# interface_dac_sma_feedback_2PS_LM317_ADC.net
KiCad netlist of a schematic drawn in EAGLE
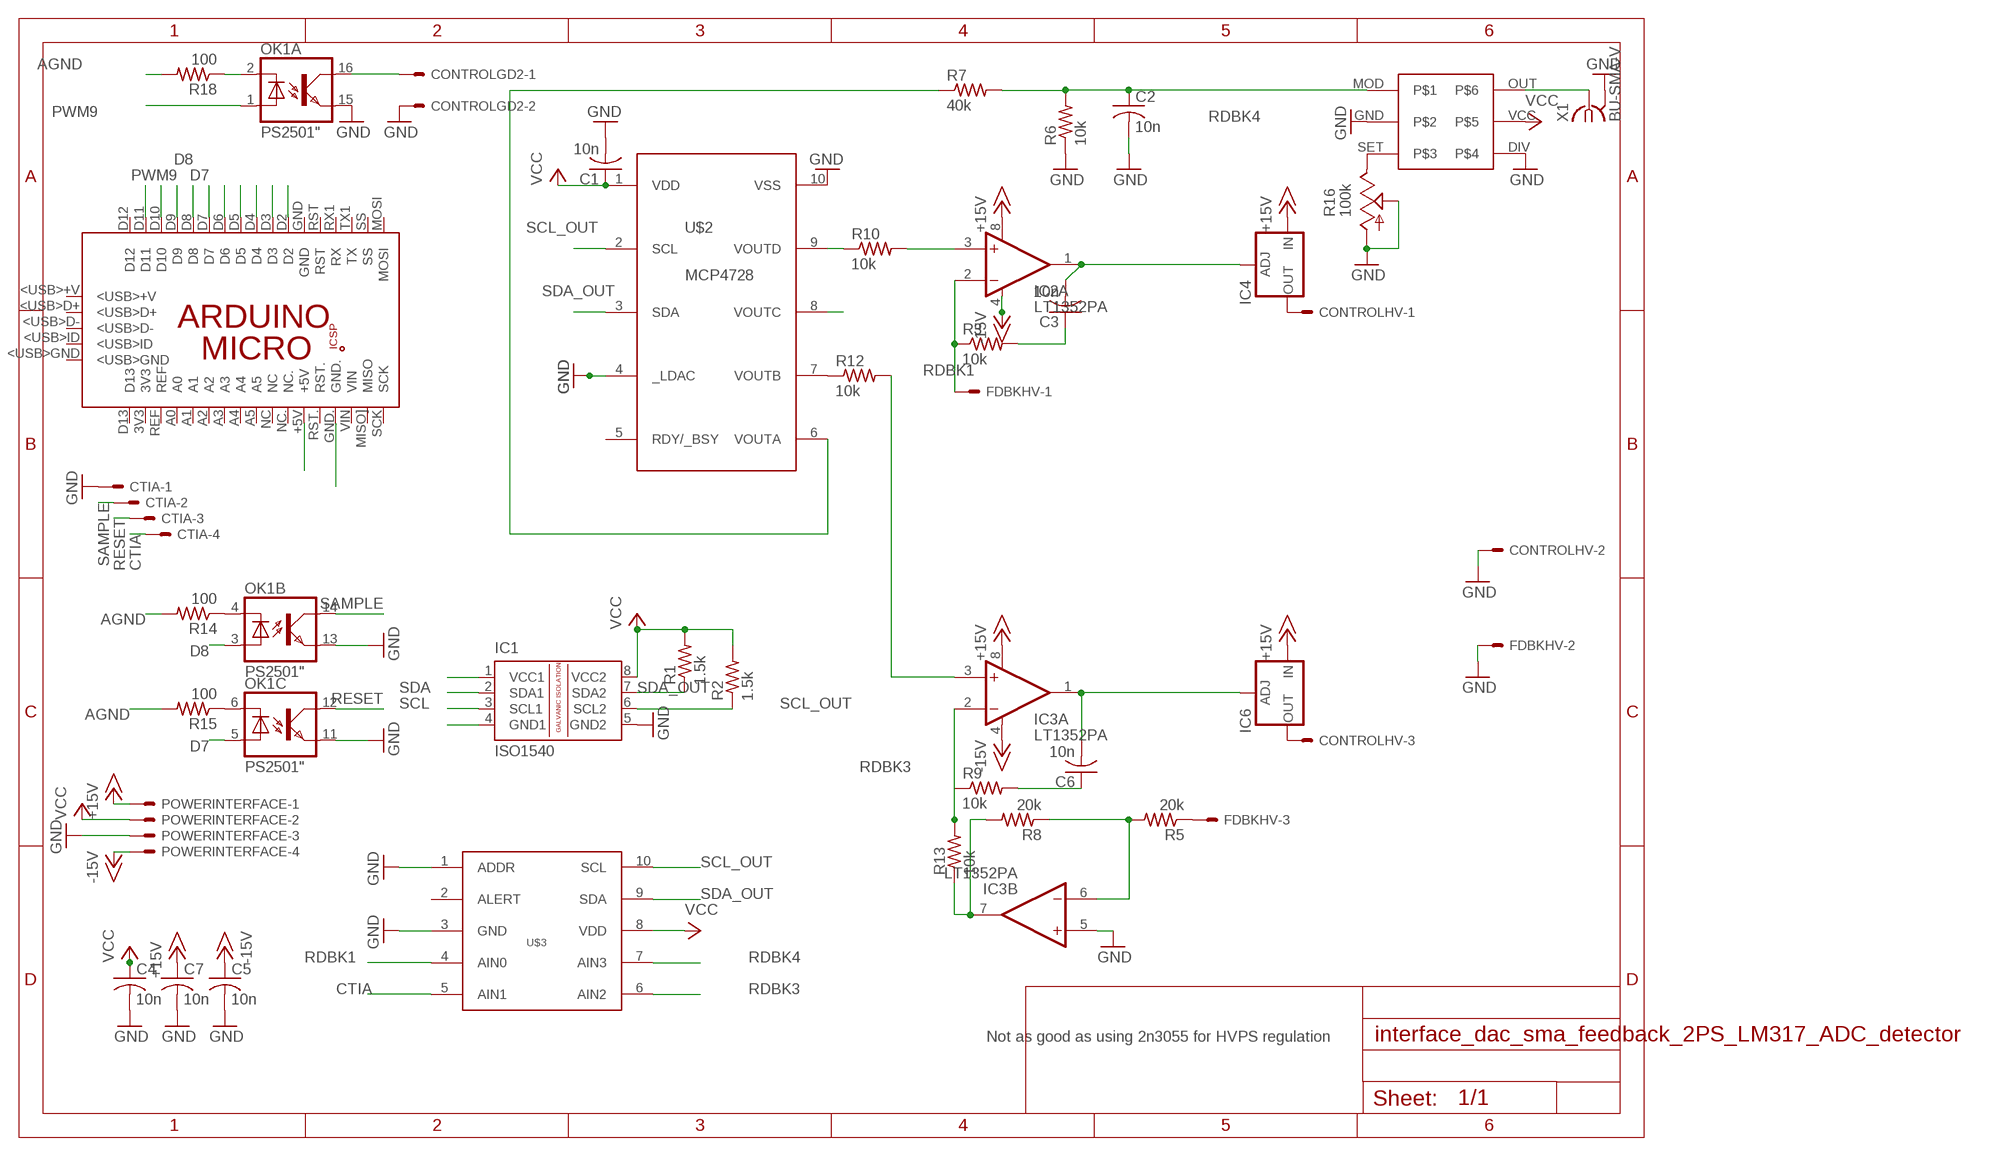
[diagram p0: schematic, sheet 1]

(export (version "E")
  (design (tool "Eeschema 10.0.6"))
  (components
    (comp (ref "C1")
      (value "10n")
      (footprint "eagle-import:C050-024X044")
      (libsource (lib "eagle-import") (part "C-US050-024X044"))
    )
    (comp (ref "C2")
      (value "10n")
      (footprint "eagle-import:C050-024X044")
      (libsource (lib "eagle-import") (part "resistor_C-US050-024X044"))
    )
    (comp (ref "C3")
      (value "10n")
      (footprint "eagle-import:C050-024X044")
      (libsource (lib "eagle-import") (part "resistor_C-US050-024X044"))
    )
    (comp (ref "C4")
      (value "10n")
      (footprint "eagle-import:C050-024X044")
      (libsource (lib "eagle-import") (part "resistor_C-US050-024X044"))
    )
    (comp (ref "C5")
      (value "10n")
      (footprint "eagle-import:C050-024X044")
      (libsource (lib "eagle-import") (part "resistor_C-US050-024X044"))
    )
    (comp (ref "C6")
      (value "10n")
      (footprint "eagle-import:C050-024X044")
      (libsource (lib "eagle-import") (part "resistor_C-US050-024X044"))
    )
    (comp (ref "C7")
      (value "10n")
      (footprint "eagle-import:C050-024X044")
      (libsource (lib "eagle-import") (part "resistor_C-US050-024X044"))
    )
    (comp (ref "CONTROLGD2")
      (value "KK-156-2")
      (footprint "eagle-import:KK-156-2")
      (libsource (lib "eagle-import") (part "KK-156-2"))
    )
    (comp (ref "CONTROLHV")
      (value "KK-156-3")
      (footprint "eagle-import:KK-156-3")
      (libsource (lib "eagle-import") (part "KK-156-3"))
    )
    (comp (ref "CTIA")
      (value "KK-156-4")
      (footprint "eagle-import:KK-156-4")
      (libsource (lib "eagle-import") (part "KK-156-4"))
    )
    (comp (ref "FDBKHV")
      (value "KK-156-3")
      (footprint "eagle-import:KK-156-3")
      (libsource (lib "eagle-import") (part "KK-156-3"))
    )
    (comp (ref "IC1")
      (value "ISO1540")
      (footprint "eagle-import:DIL08")
      (libsource (lib "eagle-import") (part "ISO1540"))
    )
    (comp (ref "IC2")
      (value "LT1352PA")
      (footprint "eagle-import:DIL08")
      (libsource (lib "eagle-import") (part "LT1352PA"))
    )
    (comp (ref "IC3")
      (value "LT1352PA")
      (footprint "eagle-import:DIL08")
      (libsource (lib "eagle-import") (part "LT1352PA"))
    )
    (comp (ref "IC4")
      (value "LM317-TO3")
      (footprint "eagle-import:TO3-K02")
      (libsource (lib "eagle-import") (part "LM317-TO3"))
    )
    (comp (ref "IC6")
      (value "LM317-TO3")
      (footprint "eagle-import:TO3-K02")
      (libsource (lib "eagle-import") (part "LM317-TO3"))
    )
    (comp (ref "OK1")
      (value "PS2501\"")
      (footprint "eagle-import:DIL16")
      (libsource (lib "eagle-import") (part "PS2501{dblquote}"))
    )
    (comp (ref "PCB1")
      (value "ARDUINO_MICRO")
      (footprint "eagle-import:ARDUINO_MICRO")
      (libsource (lib "eagle-import") (part "ARDUINO_MICRO"))
    )
    (comp (ref "POWERINTERFACE")
      (value "KK-156-4")
      (footprint "eagle-import:KK-156-4")
      (libsource (lib "eagle-import") (part "KK-156-4"))
    )
    (comp (ref "R1")
      (value "1.5k")
      (footprint "eagle-import:0207_12")
      (libsource (lib "eagle-import") (part "resistor_R-US_0207/12"))
    )
    (comp (ref "R2")
      (value "1.5k")
      (footprint "eagle-import:0207_12")
      (libsource (lib "eagle-import") (part "resistor_R-US_0207/12"))
    )
    (comp (ref "R3")
      (value "10k")
      (footprint "eagle-import:0207_12")
      (libsource (lib "eagle-import") (part "resistor_R-US_0207/12"))
    )
    (comp (ref "R5")
      (value "20k")
      (footprint "eagle-import:0207_12")
      (libsource (lib "eagle-import") (part "resistor_R-US_0207/12"))
    )
    (comp (ref "R6")
      (value "10k")
      (footprint "eagle-import:0207_12")
      (libsource (lib "eagle-import") (part "resistor_R-US_0207/12"))
    )
    (comp (ref "R7")
      (value "40k")
      (footprint "eagle-import:0207_12")
      (libsource (lib "eagle-import") (part "resistor_R-US_0207/12"))
    )
    (comp (ref "R8")
      (value "20k")
      (footprint "eagle-import:0207_12")
      (libsource (lib "eagle-import") (part "resistor_R-US_0207/12"))
    )
    (comp (ref "R9")
      (value "10k")
      (footprint "eagle-import:0207_12")
      (libsource (lib "eagle-import") (part "resistor_R-US_0207/12"))
    )
    (comp (ref "R10")
      (value "10k")
      (footprint "eagle-import:0207_12")
      (libsource (lib "eagle-import") (part "resistor_R-US_0207/12"))
    )
    (comp (ref "R12")
      (value "10k")
      (footprint "eagle-import:0207_12")
      (libsource (lib "eagle-import") (part "resistor_R-US_0207/12"))
    )
    (comp (ref "R13")
      (value "10k")
      (footprint "eagle-import:0207_12")
      (libsource (lib "eagle-import") (part "resistor_R-US_0207/12"))
    )
    (comp (ref "R14")
      (value "100")
      (footprint "eagle-import:0207_12")
      (libsource (lib "eagle-import") (part "R-US_0207/12"))
    )
    (comp (ref "R15")
      (value "100")
      (footprint "eagle-import:0207_12")
      (libsource (lib "eagle-import") (part "R-US_0207/12"))
    )
    (comp (ref "R16")
      (value "100k")
      (footprint "eagle-import:SP19L")
      (libsource (lib "eagle-import") (part "TRIM_US-B90P"))
    )
    (comp (ref "R18")
      (value "100")
      (footprint "eagle-import:0207_12")
      (libsource (lib "eagle-import") (part "R-US_0207/12"))
    )
    (comp (ref "U$1")
      (value "LTC6992")
      (footprint "eagle-import:DIL06")
      (libsource (lib "eagle-import") (part "LTC6992"))
    )
    (comp (ref "U$2")
      (value "MCP4728DIL")
      (footprint "eagle-import:DIL10")
      (libsource (lib "eagle-import") (part "MCP4728DIL"))
    )
    (comp (ref "U$3")
      (value "ADS1015DIL")
      (footprint "eagle-import:DIL10")
      (libsource (lib "eagle-import") (part "ADS1015DIL"))
    )
    (comp (ref "X1")
      (value "BU-SMA-V")
      (footprint "eagle-import:BU-SMA-V")
      (libsource (lib "eagle-import") (part "BU-SMA-V"))
    )
  )
  (nets
    (net (code "1") (name "+15V") (class "Default")
      (node (ref "C7") (pin "1") (pinfunction "1_1") (pintype "passive"))
      (node (ref "IC2") (pin "8") (pinfunction "V+_8") (pintype "power_in"))
      (node (ref "IC3") (pin "8") (pinfunction "V+_8") (pintype "power_in"))
      (node (ref "IC4") (pin "1") (pinfunction "IN_1") (pintype "input"))
      (node (ref "IC6") (pin "1") (pinfunction "IN_1") (pintype "input"))
      (node (ref "POWERINTERFACE") (pin "1") (pinfunction "S_1") (pintype "passive"))
    )
    (net (code "2") (name "-15V") (class "Default")
      (node (ref "C5") (pin "1") (pinfunction "1_1") (pintype "passive"))
      (node (ref "IC2") (pin "4") (pinfunction "V-_4") (pintype "power_in"))
      (node (ref "IC3") (pin "4") (pinfunction "V-_4") (pintype "power_in"))
      (node (ref "POWERINTERFACE") (pin "4") (pinfunction "S_4") (pintype "passive"))
    )
    (net (code "3") (name "/A+5") (class "Default")
      (node (ref "IC1") (pin "1") (pinfunction "VCC1_1") (pintype "input"))
      (node (ref "PCB1") (pin "+5V") (pinfunction "+5V_+5V") (pintype "bidirectional"))
    )
    (net (code "4") (name "/AGND") (class "Default")
      (node (ref "IC1") (pin "4") (pinfunction "GND1_4") (pintype "input"))
      (node (ref "PCB1") (pin "GND.") (pinfunction "GND._GND.") (pintype "bidirectional"))
      (node (ref "R14") (pin "2") (pinfunction "2_2") (pintype "passive"))
      (node (ref "R15") (pin "2") (pinfunction "2_2") (pintype "passive"))
      (node (ref "R18") (pin "2") (pinfunction "2_2") (pintype "passive"))
    )
    (net (code "5") (name "/CTIA") (class "Default")
      (node (ref "CTIA") (pin "4") (pinfunction "S_4") (pintype "passive"))
      (node (ref "U$3") (pin "5") (pinfunction "AIN1_5") (pintype "bidirectional"))
    )
    (net (code "6") (name "/D7") (class "Default")
      (node (ref "OK1") (pin "5") (pinfunction "A_5") (pintype "passive"))
      (node (ref "PCB1") (pin "D7") (pinfunction "D7_D7") (pintype "bidirectional"))
    )
    (net (code "7") (name "/D8") (class "Default")
      (node (ref "OK1") (pin "3") (pinfunction "A_3") (pintype "passive"))
      (node (ref "PCB1") (pin "D8") (pinfunction "D8_D8") (pintype "bidirectional"))
    )
    (net (code "8") (name "/PWM9") (class "Default")
      (node (ref "OK1") (pin "1") (pinfunction "A_1") (pintype "passive"))
      (node (ref "PCB1") (pin "D9") (pinfunction "D9_D9") (pintype "bidirectional"))
    )
    (net (code "9") (name "/RDBK1") (class "Default")
      (node (ref "FDBKHV") (pin "1") (pinfunction "S_1") (pintype "passive"))
      (node (ref "IC2") (pin "2") (pinfunction "-IN_2") (pintype "input"))
      (node (ref "R3") (pin "1") (pinfunction "1_1") (pintype "passive"))
      (node (ref "U$3") (pin "4") (pinfunction "AIN0_4") (pintype "bidirectional"))
    )
    (net (code "10") (name "/RDBK3") (class "Default")
      (node (ref "IC3") (pin "2") (pinfunction "-IN_2") (pintype "input"))
      (node (ref "R13") (pin "2") (pinfunction "2_2") (pintype "passive"))
      (node (ref "R9") (pin "1") (pinfunction "1_1") (pintype "passive"))
      (node (ref "U$3") (pin "6") (pinfunction "AIN2_6") (pintype "bidirectional"))
    )
    (net (code "11") (name "/RDBK4") (class "Default")
      (node (ref "C2") (pin "1") (pinfunction "1_1") (pintype "passive"))
      (node (ref "R6") (pin "2") (pinfunction "2_2") (pintype "passive"))
      (node (ref "R7") (pin "2") (pinfunction "2_2") (pintype "passive"))
      (node (ref "U$1") (pin "MOD") (pinfunction "P$1_MOD") (pintype "bidirectional"))
      (node (ref "U$3") (pin "7") (pinfunction "AIN3_7") (pintype "bidirectional"))
    )
    (net (code "12") (name "/RESET") (class "Default")
      (node (ref "CTIA") (pin "3") (pinfunction "S_3") (pintype "passive"))
      (node (ref "OK1") (pin "12") (pinfunction "COL_12") (pintype "passive"))
    )
    (net (code "13") (name "/SAMPLE") (class "Default")
      (node (ref "CTIA") (pin "2") (pinfunction "S_2") (pintype "passive"))
      (node (ref "OK1") (pin "14") (pinfunction "COL_14") (pintype "passive"))
    )
    (net (code "14") (name "/SCL") (class "Default")
      (node (ref "IC1") (pin "3") (pinfunction "SCL1_3") (pintype "input"))
      (node (ref "PCB1") (pin "D3") (pinfunction "D3_D3") (pintype "bidirectional"))
    )
    (net (code "15") (name "/SCL_OUT") (class "Default")
      (node (ref "IC1") (pin "6") (pinfunction "SCL2_6") (pintype "input"))
      (node (ref "R2") (pin "1") (pinfunction "1_1") (pintype "passive"))
      (node (ref "U$2") (pin "2") (pinfunction "SCL_2") (pintype "bidirectional"))
      (node (ref "U$3") (pin "10") (pinfunction "SCL_10") (pintype "bidirectional"))
    )
    (net (code "16") (name "/SDA") (class "Default")
      (node (ref "IC1") (pin "2") (pinfunction "SDA1_2") (pintype "input"))
      (node (ref "PCB1") (pin "D2") (pinfunction "D2_D2") (pintype "bidirectional"))
    )
    (net (code "17") (name "/SDA_OUT") (class "Default")
      (node (ref "IC1") (pin "7") (pinfunction "SDA2_7") (pintype "input"))
      (node (ref "R1") (pin "1") (pinfunction "1_1") (pintype "passive"))
      (node (ref "U$2") (pin "3") (pinfunction "SDA_3") (pintype "bidirectional"))
      (node (ref "U$3") (pin "9") (pinfunction "SDA_9") (pintype "bidirectional"))
    )
    (net (code "18") (name "GND") (class "Default")
      (node (ref "C1") (pin "2") (pinfunction "2_2") (pintype "passive"))
      (node (ref "C2") (pin "2") (pinfunction "2_2") (pintype "passive"))
      (node (ref "C4") (pin "2") (pinfunction "2_2") (pintype "passive"))
      (node (ref "C5") (pin "2") (pinfunction "2_2") (pintype "passive"))
      (node (ref "C7") (pin "2") (pinfunction "2_2") (pintype "passive"))
      (node (ref "CONTROLGD2") (pin "2") (pinfunction "S_2") (pintype "passive"))
      (node (ref "CONTROLHV") (pin "2") (pinfunction "S_2") (pintype "passive"))
      (node (ref "CTIA") (pin "1") (pinfunction "S_1") (pintype "passive"))
      (node (ref "FDBKHV") (pin "2") (pinfunction "S_2") (pintype "passive"))
      (node (ref "IC1") (pin "5") (pinfunction "GND2_5") (pintype "input"))
      (node (ref "IC3") (pin "5") (pinfunction "+IN_5") (pintype "input"))
      (node (ref "OK1") (pin "11") (pinfunction "EMI_11") (pintype "passive"))
      (node (ref "OK1") (pin "13") (pinfunction "EMI_13") (pintype "passive"))
      (node (ref "OK1") (pin "15") (pinfunction "EMI_15") (pintype "passive"))
      (node (ref "POWERINTERFACE") (pin "3") (pinfunction "S_3") (pintype "passive"))
      (node (ref "R16") (pin "A") (pinfunction "A_A") (pintype "passive"))
      (node (ref "R16") (pin "S") (pinfunction "S_S") (pintype "passive"))
      (node (ref "R6") (pin "1") (pinfunction "1_1") (pintype "passive"))
      (node (ref "U$1") (pin "DIV") (pinfunction "P$4_DIV") (pintype "bidirectional"))
      (node (ref "U$1") (pin "GND") (pinfunction "P$2_GND") (pintype "bidirectional"))
      (node (ref "U$2") (pin "10") (pinfunction "VSS_10") (pintype "bidirectional"))
      (node (ref "U$2") (pin "4") (pinfunction "_LDAC_4") (pintype "bidirectional"))
      (node (ref "U$3") (pin "1") (pinfunction "ADDR_1") (pintype "bidirectional"))
      (node (ref "U$3") (pin "3") (pinfunction "GND_3") (pintype "bidirectional"))
      (node (ref "X1") (pin "2") (pinfunction "2_2") (pintype "passive"))
      (node (ref "X1") (pin "3") (pinfunction "2_3") (pintype "passive"))
      (node (ref "X1") (pin "4") (pinfunction "2_4") (pintype "passive"))
      (node (ref "X1") (pin "5") (pinfunction "2_5") (pintype "passive"))
    )
    (net (code "19") (name "Net-(C3-Pad1)") (class "Default")
      (node (ref "C3") (pin "1") (pinfunction "1_1") (pintype "passive"))
      (node (ref "R3") (pin "2") (pinfunction "2_2") (pintype "passive"))
    )
    (net (code "20") (name "Net-(C6-Pad1)") (class "Default")
      (node (ref "C6") (pin "1") (pinfunction "1_1") (pintype "passive"))
      (node (ref "R9") (pin "2") (pinfunction "2_2") (pintype "passive"))
    )
    (net (code "21") (name "Net-(CONTROLGD2A-S)") (class "Default")
      (node (ref "CONTROLGD2") (pin "1") (pinfunction "S_1") (pintype "passive"))
      (node (ref "OK1") (pin "16") (pinfunction "COL_16") (pintype "passive"))
    )
    (net (code "22") (name "Net-(CONTROLHVA-S)") (class "Default")
      (node (ref "CONTROLHV") (pin "1") (pinfunction "S_1") (pintype "passive"))
      (node (ref "IC4") (pin "3") (pinfunction "OUT_3") (pintype "passive"))
    )
    (net (code "23") (name "Net-(CONTROLHVC-S)") (class "Default")
      (node (ref "CONTROLHV") (pin "3") (pinfunction "S_3") (pintype "passive"))
      (node (ref "IC6") (pin "3") (pinfunction "OUT_3") (pintype "passive"))
    )
    (net (code "24") (name "Net-(FDBKHVC-S)") (class "Default")
      (node (ref "FDBKHV") (pin "3") (pinfunction "S_3") (pintype "passive"))
      (node (ref "R5") (pin "1") (pinfunction "1_1") (pintype "passive"))
    )
    (net (code "25") (name "Net-(IC2A-+IN)") (class "Default")
      (node (ref "IC2") (pin "3") (pinfunction "+IN_3") (pintype "input"))
      (node (ref "R10") (pin "2") (pinfunction "2_2") (pintype "passive"))
    )
    (net (code "26") (name "Net-(IC2A-OUT)") (class "Default")
      (node (ref "C3") (pin "2") (pinfunction "2_2") (pintype "passive"))
      (node (ref "IC2") (pin "1") (pinfunction "OUT_1") (pintype "output"))
      (node (ref "IC4") (pin "2") (pinfunction "ADJ_2") (pintype "input"))
    )
    (net (code "27") (name "Net-(IC3A-+IN)") (class "Default")
      (node (ref "IC3") (pin "3") (pinfunction "+IN_3") (pintype "input"))
      (node (ref "R12") (pin "2") (pinfunction "2_2") (pintype "passive"))
    )
    (net (code "28") (name "Net-(IC3A-OUT)") (class "Default")
      (node (ref "C6") (pin "2") (pinfunction "2_2") (pintype "passive"))
      (node (ref "IC3") (pin "1") (pinfunction "OUT_1") (pintype "output"))
      (node (ref "IC6") (pin "2") (pinfunction "ADJ_2") (pintype "input"))
    )
    (net (code "29") (name "Net-(IC3B--IN)") (class "Default")
      (node (ref "IC3") (pin "6") (pinfunction "-IN_6") (pintype "input"))
      (node (ref "R5") (pin "2") (pinfunction "2_2") (pintype "passive"))
      (node (ref "R8") (pin "1") (pinfunction "1_1") (pintype "passive"))
    )
    (net (code "30") (name "Net-(IC3B-OUT)") (class "Default")
      (node (ref "IC3") (pin "7") (pinfunction "OUT_7") (pintype "output"))
      (node (ref "R13") (pin "1") (pinfunction "1_1") (pintype "passive"))
      (node (ref "R8") (pin "2") (pinfunction "2_2") (pintype "passive"))
    )
    (net (code "31") (name "Net-(OK1A-C)") (class "Default")
      (node (ref "OK1") (pin "2") (pinfunction "C_2") (pintype "passive"))
      (node (ref "R18") (pin "1") (pinfunction "1_1") (pintype "passive"))
    )
    (net (code "32") (name "Net-(OK1B-C)") (class "Default")
      (node (ref "OK1") (pin "4") (pinfunction "C_4") (pintype "passive"))
      (node (ref "R14") (pin "1") (pinfunction "1_1") (pintype "passive"))
    )
    (net (code "33") (name "Net-(OK1C-C)") (class "Default")
      (node (ref "OK1") (pin "6") (pinfunction "C_6") (pintype "passive"))
      (node (ref "R15") (pin "1") (pinfunction "1_1") (pintype "passive"))
    )
    (net (code "34") (name "Net-(U$1-P$3)") (class "Default")
      (node (ref "R16") (pin "E") (pinfunction "E_E") (pintype "passive"))
      (node (ref "U$1") (pin "SET") (pinfunction "P$3_SET") (pintype "bidirectional"))
    )
    (net (code "35") (name "Net-(U$1-P$6)") (class "Default")
      (node (ref "U$1") (pin "OUT") (pinfunction "P$6_OUT") (pintype "bidirectional"))
      (node (ref "X1") (pin "1") (pinfunction "1_1") (pintype "passive"))
    )
    (net (code "36") (name "Net-(U$2-VOUTA)") (class "Default")
      (node (ref "R7") (pin "1") (pinfunction "1_1") (pintype "passive"))
      (node (ref "U$2") (pin "6") (pinfunction "VOUTA_6") (pintype "bidirectional"))
    )
    (net (code "37") (name "Net-(U$2-VOUTB)") (class "Default")
      (node (ref "R12") (pin "1") (pinfunction "1_1") (pintype "passive"))
      (node (ref "U$2") (pin "7") (pinfunction "VOUTB_7") (pintype "bidirectional"))
    )
    (net (code "38") (name "Net-(U$2-VOUTD)") (class "Default")
      (node (ref "R10") (pin "1") (pinfunction "1_1") (pintype "passive"))
      (node (ref "U$2") (pin "9") (pinfunction "VOUTD_9") (pintype "bidirectional"))
    )
    (net (code "39") (name "VCC") (class "Default")
      (node (ref "C1") (pin "1") (pinfunction "1_1") (pintype "passive"))
      (node (ref "C4") (pin "1") (pinfunction "1_1") (pintype "passive"))
      (node (ref "IC1") (pin "8") (pinfunction "VCC2_8") (pintype "input"))
      (node (ref "POWERINTERFACE") (pin "2") (pinfunction "S_2") (pintype "passive"))
      (node (ref "R1") (pin "2") (pinfunction "2_2") (pintype "passive"))
      (node (ref "R2") (pin "2") (pinfunction "2_2") (pintype "passive"))
      (node (ref "U$1") (pin "VCC") (pinfunction "P$5_VCC") (pintype "bidirectional"))
      (node (ref "U$2") (pin "1") (pinfunction "VDD_1") (pintype "bidirectional"))
      (node (ref "U$3") (pin "8") (pinfunction "VDD_8") (pintype "bidirectional"))
    )
    (net (code "40") (name "unconnected-(PCB1-MISO-PadMISO])") (class "Default")
      (node (ref "PCB1") (pin "MISO]") (pinfunction "MISO_MISO]") (pintype "bidirectional"))
    )
    (net (code "41") (name "unconnected-(PCB1-Pad3V3)") (class "Default")
      (node (ref "PCB1") (pin "3V3") (pinfunction "3V3_3V3") (pintype "bidirectional"))
    )
    (net (code "42") (name "unconnected-(PCB1-Pad5V)") (class "Default")
      (node (ref "PCB1") (pin "5V") (pinfunction "5V_5V") (pintype "bidirectional"))
    )
    (net (code "43") (name "unconnected-(PCB1-Pad<USB>+V)") (class "Default")
      (node (ref "PCB1") (pin "<USB>+V") (pinfunction "<USB>+V_<USB>+V") (pintype "bidirectional"))
    )
    (net (code "44") (name "unconnected-(PCB1-Pad<USB>D+)") (class "Default")
      (node (ref "PCB1") (pin "<USB>D+") (pinfunction "<USB>D+_<USB>D+") (pintype "bidirectional"))
    )
    (net (code "45") (name "unconnected-(PCB1-Pad<USB>D-)") (class "Default")
      (node (ref "PCB1") (pin "<USB>D-") (pinfunction "<USB>D-_<USB>D-") (pintype "bidirectional"))
    )
    (net (code "46") (name "unconnected-(PCB1-Pad<USB>GND)") (class "Default")
      (node (ref "PCB1") (pin "<USB>GND") (pinfunction "<USB>GND_<USB>GND") (pintype "bidirectional"))
    )
    (net (code "47") (name "unconnected-(PCB1-Pad<USB>ID)") (class "Default")
      (node (ref "PCB1") (pin "<USB>ID") (pinfunction "<USB>ID_<USB>ID") (pintype "bidirectional"))
    )
    (net (code "48") (name "unconnected-(PCB1-PadA0)") (class "Default")
      (node (ref "PCB1") (pin "A0") (pinfunction "A0_A0") (pintype "bidirectional"))
    )
    (net (code "49") (name "unconnected-(PCB1-PadA1)") (class "Default")
      (node (ref "PCB1") (pin "A1") (pinfunction "A1_A1") (pintype "bidirectional"))
    )
    (net (code "50") (name "unconnected-(PCB1-PadA2)") (class "Default")
      (node (ref "PCB1") (pin "A2") (pinfunction "A2_A2") (pintype "bidirectional"))
    )
    (net (code "51") (name "unconnected-(PCB1-PadA3)") (class "Default")
      (node (ref "PCB1") (pin "A3") (pinfunction "A3_A3") (pintype "bidirectional"))
    )
    (net (code "52") (name "unconnected-(PCB1-PadA4)") (class "Default")
      (node (ref "PCB1") (pin "A4") (pinfunction "A4_A4") (pintype "bidirectional"))
    )
    (net (code "53") (name "unconnected-(PCB1-PadA5)") (class "Default")
      (node (ref "PCB1") (pin "A5") (pinfunction "A5_A5") (pintype "bidirectional"))
    )
    (net (code "54") (name "unconnected-(PCB1-PadD4)") (class "Default")
      (node (ref "PCB1") (pin "D4") (pinfunction "D4_D4") (pintype "bidirectional"))
    )
    (net (code "55") (name "unconnected-(PCB1-PadD5)") (class "Default")
      (node (ref "PCB1") (pin "D5") (pinfunction "D5_D5") (pintype "bidirectional"))
    )
    (net (code "56") (name "unconnected-(PCB1-PadD6)") (class "Default")
      (node (ref "PCB1") (pin "D6") (pinfunction "D6_D6") (pintype "bidirectional"))
    )
    (net (code "57") (name "unconnected-(PCB1-PadD10)") (class "Default")
      (node (ref "PCB1") (pin "D10") (pinfunction "D10_D10") (pintype "bidirectional"))
    )
    (net (code "58") (name "unconnected-(PCB1-PadD11)") (class "Default")
      (node (ref "PCB1") (pin "D11") (pinfunction "D11_D11") (pintype "bidirectional"))
    )
    (net (code "59") (name "unconnected-(PCB1-PadD12)") (class "Default")
      (node (ref "PCB1") (pin "D12") (pinfunction "D12_D12") (pintype "bidirectional"))
    )
    (net (code "60") (name "unconnected-(PCB1-PadD13)") (class "Default")
      (node (ref "PCB1") (pin "D13") (pinfunction "D13_D13") (pintype "bidirectional"))
    )
    (net (code "61") (name "unconnected-(PCB1-PadGND)") (class "Default")
      (node (ref "PCB1") (pin "GND") (pinfunction "GND_GND") (pintype "bidirectional"))
    )
    (net (code "62") (name "unconnected-(PCB1-PadGND_)") (class "Default")
      (node (ref "PCB1") (pin "GND_") (pinfunction "GND__GND_") (pintype "bidirectional"))
    )
    (net (code "63") (name "unconnected-(PCB1-PadMISO.)") (class "Default")
      (node (ref "PCB1") (pin "MISO.") (pinfunction "MISO._MISO.") (pintype "bidirectional"))
    )
    (net (code "64") (name "unconnected-(PCB1-PadMOSI)") (class "Default")
      (node (ref "PCB1") (pin "MOSI") (pinfunction "MOSI_MOSI") (pintype "bidirectional"))
    )
    (net (code "65") (name "unconnected-(PCB1-PadMOSI.)") (class "Default")
      (node (ref "PCB1") (pin "MOSI.") (pinfunction "MOSI._MOSI.") (pintype "bidirectional"))
    )
    (net (code "66") (name "unconnected-(PCB1-PadNC)") (class "Default")
      (node (ref "PCB1") (pin "NC") (pinfunction "NC_NC") (pintype "bidirectional"))
    )
    (net (code "67") (name "unconnected-(PCB1-PadNC.)") (class "Default")
      (node (ref "PCB1") (pin "NC.") (pinfunction "NC._NC.") (pintype "bidirectional"))
    )
    (net (code "68") (name "unconnected-(PCB1-PadREF)") (class "Default")
      (node (ref "PCB1") (pin "REF") (pinfunction "REF_REF") (pintype "bidirectional"))
    )
    (net (code "69") (name "unconnected-(PCB1-PadRESET..)") (class "Default")
      (node (ref "PCB1") (pin "RESET..") (pinfunction "RESET.._RESET..") (pintype "bidirectional"))
    )
    (net (code "70") (name "unconnected-(PCB1-PadRST)") (class "Default")
      (node (ref "PCB1") (pin "RST") (pinfunction "RST_RST") (pintype "bidirectional"))
    )
    (net (code "71") (name "unconnected-(PCB1-PadRST.)") (class "Default")
      (node (ref "PCB1") (pin "RST.") (pinfunction "RST._RST.") (pintype "bidirectional"))
    )
    (net (code "72") (name "unconnected-(PCB1-PadSCK)") (class "Default")
      (node (ref "PCB1") (pin "SCK") (pinfunction "SCK_SCK") (pintype "bidirectional"))
    )
    (net (code "73") (name "unconnected-(PCB1-PadSCK.)") (class "Default")
      (node (ref "PCB1") (pin "SCK.") (pinfunction "SCK._SCK.") (pintype "bidirectional"))
    )
    (net (code "74") (name "unconnected-(PCB1-PadSS)") (class "Default")
      (node (ref "PCB1") (pin "SS") (pinfunction "SS_SS") (pintype "bidirectional"))
    )
    (net (code "75") (name "unconnected-(PCB1-PadVIN)") (class "Default")
      (node (ref "PCB1") (pin "VIN") (pinfunction "VIN_VIN") (pintype "bidirectional"))
    )
    (net (code "76") (name "unconnected-(PCB1-RX-PadRX1)") (class "Default")
      (node (ref "PCB1") (pin "RX1") (pinfunction "RX_RX1") (pintype "bidirectional"))
    )
    (net (code "77") (name "unconnected-(PCB1-TX-PadTX1)") (class "Default")
      (node (ref "PCB1") (pin "TX1") (pinfunction "TX_TX1") (pintype "bidirectional"))
    )
    (net (code "78") (name "unconnected-(U$2-RDY{slash}_BSY-Pad5)") (class "Default")
      (node (ref "U$2") (pin "5") (pinfunction "RDY/_BSY_5") (pintype "bidirectional"))
    )
    (net (code "79") (name "unconnected-(U$2-VOUTC-Pad8)") (class "Default")
      (node (ref "U$2") (pin "8") (pinfunction "VOUTC_8") (pintype "bidirectional"))
    )
    (net (code "80") (name "unconnected-(U$3-ALERT-Pad2)") (class "Default")
      (node (ref "U$3") (pin "2") (pinfunction "ALERT_2") (pintype "bidirectional"))
    )
  )
)
